# led-strip-v2.net
KiCad netlist of a schematic drawn in EAGLE
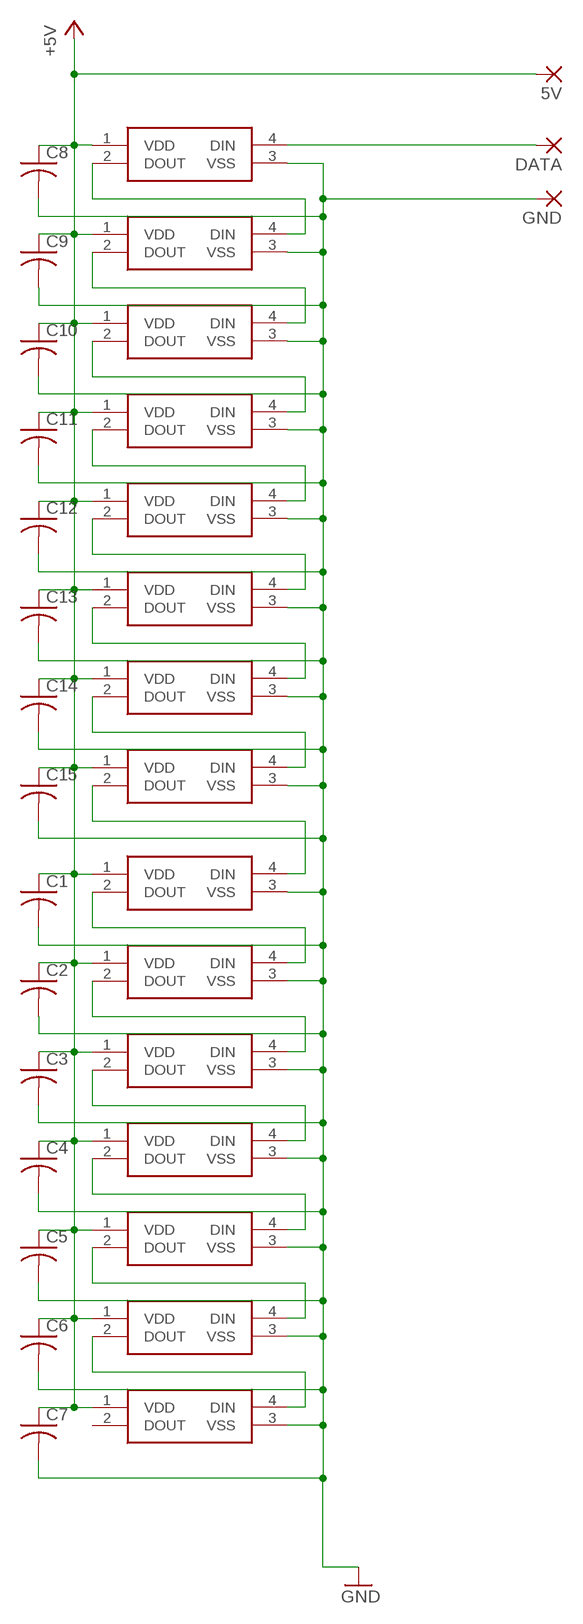
[diagram p0: schematic, sheet 1]

(export (version "E")
  (design (tool "Eeschema 10.0.6"))
  (components
    (comp (ref "5V")
      (value "1,6/0,8")
      (footprint "eagle-import:1,6_0,8")
      (libsource (lib "eagle-import") (part "1,6/0,8"))
    )
    (comp (ref "C1")
      (value "C-USC0805")
      (footprint "eagle-import:C0805")
      (libsource (lib "eagle-import") (part "C-USC0805"))
    )
    (comp (ref "C2")
      (value "C-USC0805")
      (footprint "eagle-import:C0805")
      (libsource (lib "eagle-import") (part "C-USC0805"))
    )
    (comp (ref "C3")
      (value "C-USC0805")
      (footprint "eagle-import:C0805")
      (libsource (lib "eagle-import") (part "C-USC0805"))
    )
    (comp (ref "C4")
      (value "C-USC0805")
      (footprint "eagle-import:C0805")
      (libsource (lib "eagle-import") (part "C-USC0805"))
    )
    (comp (ref "C5")
      (value "C-USC0805")
      (footprint "eagle-import:C0805")
      (libsource (lib "eagle-import") (part "C-USC0805"))
    )
    (comp (ref "C6")
      (value "C-USC0805")
      (footprint "eagle-import:C0805")
      (libsource (lib "eagle-import") (part "C-USC0805"))
    )
    (comp (ref "C7")
      (value "C-USC0805")
      (footprint "eagle-import:C0805")
      (libsource (lib "eagle-import") (part "C-USC0805"))
    )
    (comp (ref "C8")
      (value "C-USC0805")
      (footprint "eagle-import:C0805")
      (libsource (lib "eagle-import") (part "C-USC0805"))
    )
    (comp (ref "C9")
      (value "C-USC0805")
      (footprint "eagle-import:C0805")
      (libsource (lib "eagle-import") (part "C-USC0805"))
    )
    (comp (ref "C10")
      (value "C-USC0805")
      (footprint "eagle-import:C0805")
      (libsource (lib "eagle-import") (part "C-USC0805"))
    )
    (comp (ref "C11")
      (value "C-USC0805")
      (footprint "eagle-import:C0805")
      (libsource (lib "eagle-import") (part "C-USC0805"))
    )
    (comp (ref "C12")
      (value "C-USC0805")
      (footprint "eagle-import:C0805")
      (libsource (lib "eagle-import") (part "C-USC0805"))
    )
    (comp (ref "C13")
      (value "C-USC0805")
      (footprint "eagle-import:C0805")
      (libsource (lib "eagle-import") (part "C-USC0805"))
    )
    (comp (ref "C14")
      (value "C-USC0805")
      (footprint "eagle-import:C0805")
      (libsource (lib "eagle-import") (part "C-USC0805"))
    )
    (comp (ref "C15")
      (value "C-USC0805")
      (footprint "eagle-import:C0805")
      (libsource (lib "eagle-import") (part "C-USC0805"))
    )
    (comp (ref "DATA")
      (value "1,6/0,8")
      (footprint "eagle-import:1,6_0,8")
      (libsource (lib "eagle-import") (part "1,6/0,8"))
    )
    (comp (ref "GND")
      (value "1,6/0,8")
      (footprint "eagle-import:1,6_0,8")
      (libsource (lib "eagle-import") (part "1,6/0,8"))
    )
    (comp (ref "LED1")
      (value "1655")
      (footprint "eagle-import:WS2812B_1")
      (libsource (lib "eagle-import") (part "sk6812_1655"))
    )
    (comp (ref "LED2")
      (value "1655")
      (footprint "eagle-import:WS2812B_1")
      (libsource (lib "eagle-import") (part "1655"))
    )
    (comp (ref "LED3")
      (value "1655")
      (footprint "eagle-import:WS2812B_1")
      (libsource (lib "eagle-import") (part "1655"))
    )
    (comp (ref "LED4")
      (value "1655")
      (footprint "eagle-import:WS2812B_1")
      (libsource (lib "eagle-import") (part "1655"))
    )
    (comp (ref "LED5")
      (value "1655")
      (footprint "eagle-import:WS2812B_1")
      (libsource (lib "eagle-import") (part "1655"))
    )
    (comp (ref "LED6")
      (value "1655")
      (footprint "eagle-import:WS2812B_1")
      (libsource (lib "eagle-import") (part "1655"))
    )
    (comp (ref "LED7")
      (value "1655")
      (footprint "eagle-import:WS2812B_1")
      (libsource (lib "eagle-import") (part "1655"))
    )
    (comp (ref "LED8")
      (value "1655")
      (footprint "eagle-import:WS2812B_1")
      (libsource (lib "eagle-import") (part "1655"))
    )
    (comp (ref "LED9")
      (value "1655")
      (footprint "eagle-import:WS2812B_1")
      (libsource (lib "eagle-import") (part "1655"))
    )
    (comp (ref "LED10")
      (value "1655")
      (footprint "eagle-import:WS2812B_1")
      (libsource (lib "eagle-import") (part "1655"))
    )
    (comp (ref "LED11")
      (value "1655")
      (footprint "eagle-import:WS2812B_1")
      (libsource (lib "eagle-import") (part "1655"))
    )
    (comp (ref "LED12")
      (value "1655")
      (footprint "eagle-import:WS2812B_1")
      (libsource (lib "eagle-import") (part "1655"))
    )
    (comp (ref "LED13")
      (value "1655")
      (footprint "eagle-import:WS2812B_1")
      (libsource (lib "eagle-import") (part "1655"))
    )
    (comp (ref "LED14")
      (value "1655")
      (footprint "eagle-import:WS2812B_1")
      (libsource (lib "eagle-import") (part "1655"))
    )
    (comp (ref "LED15")
      (value "1655")
      (footprint "eagle-import:WS2812B_1")
      (libsource (lib "eagle-import") (part "1655"))
    )
  )
  (nets
    (net (code "1") (name "+5V") (class "Default")
      (node (ref "5V") (pin "1") (pinfunction "P_1") (pintype "passive"))
      (node (ref "C1") (pin "1") (pinfunction "1_1") (pintype "passive"))
      (node (ref "C10") (pin "1") (pinfunction "1_1") (pintype "passive"))
      (node (ref "C11") (pin "1") (pinfunction "1_1") (pintype "passive"))
      (node (ref "C12") (pin "1") (pinfunction "1_1") (pintype "passive"))
      (node (ref "C13") (pin "1") (pinfunction "1_1") (pintype "passive"))
      (node (ref "C14") (pin "1") (pinfunction "1_1") (pintype "passive"))
      (node (ref "C15") (pin "1") (pinfunction "1_1") (pintype "passive"))
      (node (ref "C2") (pin "1") (pinfunction "1_1") (pintype "passive"))
      (node (ref "C3") (pin "1") (pinfunction "1_1") (pintype "passive"))
      (node (ref "C4") (pin "1") (pinfunction "1_1") (pintype "passive"))
      (node (ref "C5") (pin "1") (pinfunction "1_1") (pintype "passive"))
      (node (ref "C6") (pin "1") (pinfunction "1_1") (pintype "passive"))
      (node (ref "C7") (pin "1") (pinfunction "1_1") (pintype "passive"))
      (node (ref "C8") (pin "1") (pinfunction "1_1") (pintype "passive"))
      (node (ref "C9") (pin "1") (pinfunction "1_1") (pintype "passive"))
      (node (ref "LED1") (pin "1") (pinfunction "VDD_1") (pintype "bidirectional"))
      (node (ref "LED10") (pin "1") (pinfunction "VDD_1") (pintype "bidirectional"))
      (node (ref "LED11") (pin "1") (pinfunction "VDD_1") (pintype "bidirectional"))
      (node (ref "LED12") (pin "1") (pinfunction "VDD_1") (pintype "bidirectional"))
      (node (ref "LED13") (pin "1") (pinfunction "VDD_1") (pintype "bidirectional"))
      (node (ref "LED14") (pin "1") (pinfunction "VDD_1") (pintype "bidirectional"))
      (node (ref "LED15") (pin "1") (pinfunction "VDD_1") (pintype "bidirectional"))
      (node (ref "LED2") (pin "1") (pinfunction "VDD_1") (pintype "bidirectional"))
      (node (ref "LED3") (pin "1") (pinfunction "VDD_1") (pintype "bidirectional"))
      (node (ref "LED4") (pin "1") (pinfunction "VDD_1") (pintype "bidirectional"))
      (node (ref "LED5") (pin "1") (pinfunction "VDD_1") (pintype "bidirectional"))
      (node (ref "LED6") (pin "1") (pinfunction "VDD_1") (pintype "bidirectional"))
      (node (ref "LED7") (pin "1") (pinfunction "VDD_1") (pintype "bidirectional"))
      (node (ref "LED8") (pin "1") (pinfunction "VDD_1") (pintype "bidirectional"))
      (node (ref "LED9") (pin "1") (pinfunction "VDD_1") (pintype "bidirectional"))
    )
    (net (code "2") (name "GND") (class "Default")
      (node (ref "C1") (pin "2") (pinfunction "2_2") (pintype "passive"))
      (node (ref "C10") (pin "2") (pinfunction "2_2") (pintype "passive"))
      (node (ref "C11") (pin "2") (pinfunction "2_2") (pintype "passive"))
      (node (ref "C12") (pin "2") (pinfunction "2_2") (pintype "passive"))
      (node (ref "C13") (pin "2") (pinfunction "2_2") (pintype "passive"))
      (node (ref "C14") (pin "2") (pinfunction "2_2") (pintype "passive"))
      (node (ref "C15") (pin "2") (pinfunction "2_2") (pintype "passive"))
      (node (ref "C2") (pin "2") (pinfunction "2_2") (pintype "passive"))
      (node (ref "C3") (pin "2") (pinfunction "2_2") (pintype "passive"))
      (node (ref "C4") (pin "2") (pinfunction "2_2") (pintype "passive"))
      (node (ref "C5") (pin "2") (pinfunction "2_2") (pintype "passive"))
      (node (ref "C6") (pin "2") (pinfunction "2_2") (pintype "passive"))
      (node (ref "C7") (pin "2") (pinfunction "2_2") (pintype "passive"))
      (node (ref "C8") (pin "2") (pinfunction "2_2") (pintype "passive"))
      (node (ref "C9") (pin "2") (pinfunction "2_2") (pintype "passive"))
      (node (ref "GND") (pin "1") (pinfunction "P_1") (pintype "passive"))
      (node (ref "LED1") (pin "3") (pinfunction "VSS_3") (pintype "bidirectional"))
      (node (ref "LED10") (pin "3") (pinfunction "VSS_3") (pintype "bidirectional"))
      (node (ref "LED11") (pin "3") (pinfunction "VSS_3") (pintype "bidirectional"))
      (node (ref "LED12") (pin "3") (pinfunction "VSS_3") (pintype "bidirectional"))
      (node (ref "LED13") (pin "3") (pinfunction "VSS_3") (pintype "bidirectional"))
      (node (ref "LED14") (pin "3") (pinfunction "VSS_3") (pintype "bidirectional"))
      (node (ref "LED15") (pin "3") (pinfunction "VSS_3") (pintype "bidirectional"))
      (node (ref "LED2") (pin "3") (pinfunction "VSS_3") (pintype "bidirectional"))
      (node (ref "LED3") (pin "3") (pinfunction "VSS_3") (pintype "bidirectional"))
      (node (ref "LED4") (pin "3") (pinfunction "VSS_3") (pintype "bidirectional"))
      (node (ref "LED5") (pin "3") (pinfunction "VSS_3") (pintype "bidirectional"))
      (node (ref "LED6") (pin "3") (pinfunction "VSS_3") (pintype "bidirectional"))
      (node (ref "LED7") (pin "3") (pinfunction "VSS_3") (pintype "bidirectional"))
      (node (ref "LED8") (pin "3") (pinfunction "VSS_3") (pintype "bidirectional"))
      (node (ref "LED9") (pin "3") (pinfunction "VSS_3") (pintype "bidirectional"))
    )
    (net (code "3") (name "Net-(DATA-P)") (class "Default")
      (node (ref "DATA") (pin "1") (pinfunction "P_1") (pintype "passive"))
      (node (ref "LED1") (pin "4") (pinfunction "DIN_4") (pintype "bidirectional"))
    )
    (net (code "4") (name "Net-(LED1-DOUT)") (class "Default")
      (node (ref "LED1") (pin "2") (pinfunction "DOUT_2") (pintype "bidirectional"))
      (node (ref "LED2") (pin "4") (pinfunction "DIN_4") (pintype "bidirectional"))
    )
    (net (code "5") (name "Net-(LED2-DOUT)") (class "Default")
      (node (ref "LED2") (pin "2") (pinfunction "DOUT_2") (pintype "bidirectional"))
      (node (ref "LED3") (pin "4") (pinfunction "DIN_4") (pintype "bidirectional"))
    )
    (net (code "6") (name "Net-(LED3-DOUT)") (class "Default")
      (node (ref "LED3") (pin "2") (pinfunction "DOUT_2") (pintype "bidirectional"))
      (node (ref "LED4") (pin "4") (pinfunction "DIN_4") (pintype "bidirectional"))
    )
    (net (code "7") (name "Net-(LED4-DOUT)") (class "Default")
      (node (ref "LED4") (pin "2") (pinfunction "DOUT_2") (pintype "bidirectional"))
      (node (ref "LED5") (pin "4") (pinfunction "DIN_4") (pintype "bidirectional"))
    )
    (net (code "8") (name "Net-(LED5-DOUT)") (class "Default")
      (node (ref "LED5") (pin "2") (pinfunction "DOUT_2") (pintype "bidirectional"))
      (node (ref "LED6") (pin "4") (pinfunction "DIN_4") (pintype "bidirectional"))
    )
    (net (code "9") (name "Net-(LED6-DOUT)") (class "Default")
      (node (ref "LED6") (pin "2") (pinfunction "DOUT_2") (pintype "bidirectional"))
      (node (ref "LED7") (pin "4") (pinfunction "DIN_4") (pintype "bidirectional"))
    )
    (net (code "10") (name "Net-(LED7-DOUT)") (class "Default")
      (node (ref "LED7") (pin "2") (pinfunction "DOUT_2") (pintype "bidirectional"))
      (node (ref "LED8") (pin "4") (pinfunction "DIN_4") (pintype "bidirectional"))
    )
    (net (code "11") (name "Net-(LED8-DOUT)") (class "Default")
      (node (ref "LED8") (pin "2") (pinfunction "DOUT_2") (pintype "bidirectional"))
      (node (ref "LED9") (pin "4") (pinfunction "DIN_4") (pintype "bidirectional"))
    )
    (net (code "12") (name "Net-(LED10-DIN)") (class "Default")
      (node (ref "LED10") (pin "4") (pinfunction "DIN_4") (pintype "bidirectional"))
      (node (ref "LED9") (pin "2") (pinfunction "DOUT_2") (pintype "bidirectional"))
    )
    (net (code "13") (name "Net-(LED10-DOUT)") (class "Default")
      (node (ref "LED10") (pin "2") (pinfunction "DOUT_2") (pintype "bidirectional"))
      (node (ref "LED11") (pin "4") (pinfunction "DIN_4") (pintype "bidirectional"))
    )
    (net (code "14") (name "Net-(LED11-DOUT)") (class "Default")
      (node (ref "LED11") (pin "2") (pinfunction "DOUT_2") (pintype "bidirectional"))
      (node (ref "LED12") (pin "4") (pinfunction "DIN_4") (pintype "bidirectional"))
    )
    (net (code "15") (name "Net-(LED12-DOUT)") (class "Default")
      (node (ref "LED12") (pin "2") (pinfunction "DOUT_2") (pintype "bidirectional"))
      (node (ref "LED13") (pin "4") (pinfunction "DIN_4") (pintype "bidirectional"))
    )
    (net (code "16") (name "Net-(LED13-DOUT)") (class "Default")
      (node (ref "LED13") (pin "2") (pinfunction "DOUT_2") (pintype "bidirectional"))
      (node (ref "LED14") (pin "4") (pinfunction "DIN_4") (pintype "bidirectional"))
    )
    (net (code "17") (name "Net-(LED14-DOUT)") (class "Default")
      (node (ref "LED14") (pin "2") (pinfunction "DOUT_2") (pintype "bidirectional"))
      (node (ref "LED15") (pin "4") (pinfunction "DIN_4") (pintype "bidirectional"))
    )
    (net (code "18") (name "unconnected-(LED15-DOUT-Pad2)") (class "Default")
      (node (ref "LED15") (pin "2") (pinfunction "DOUT_2") (pintype "bidirectional"))
    )
  )
)
